# SCH.net
KiCad netlist of a schematic drawn in EasyEDA
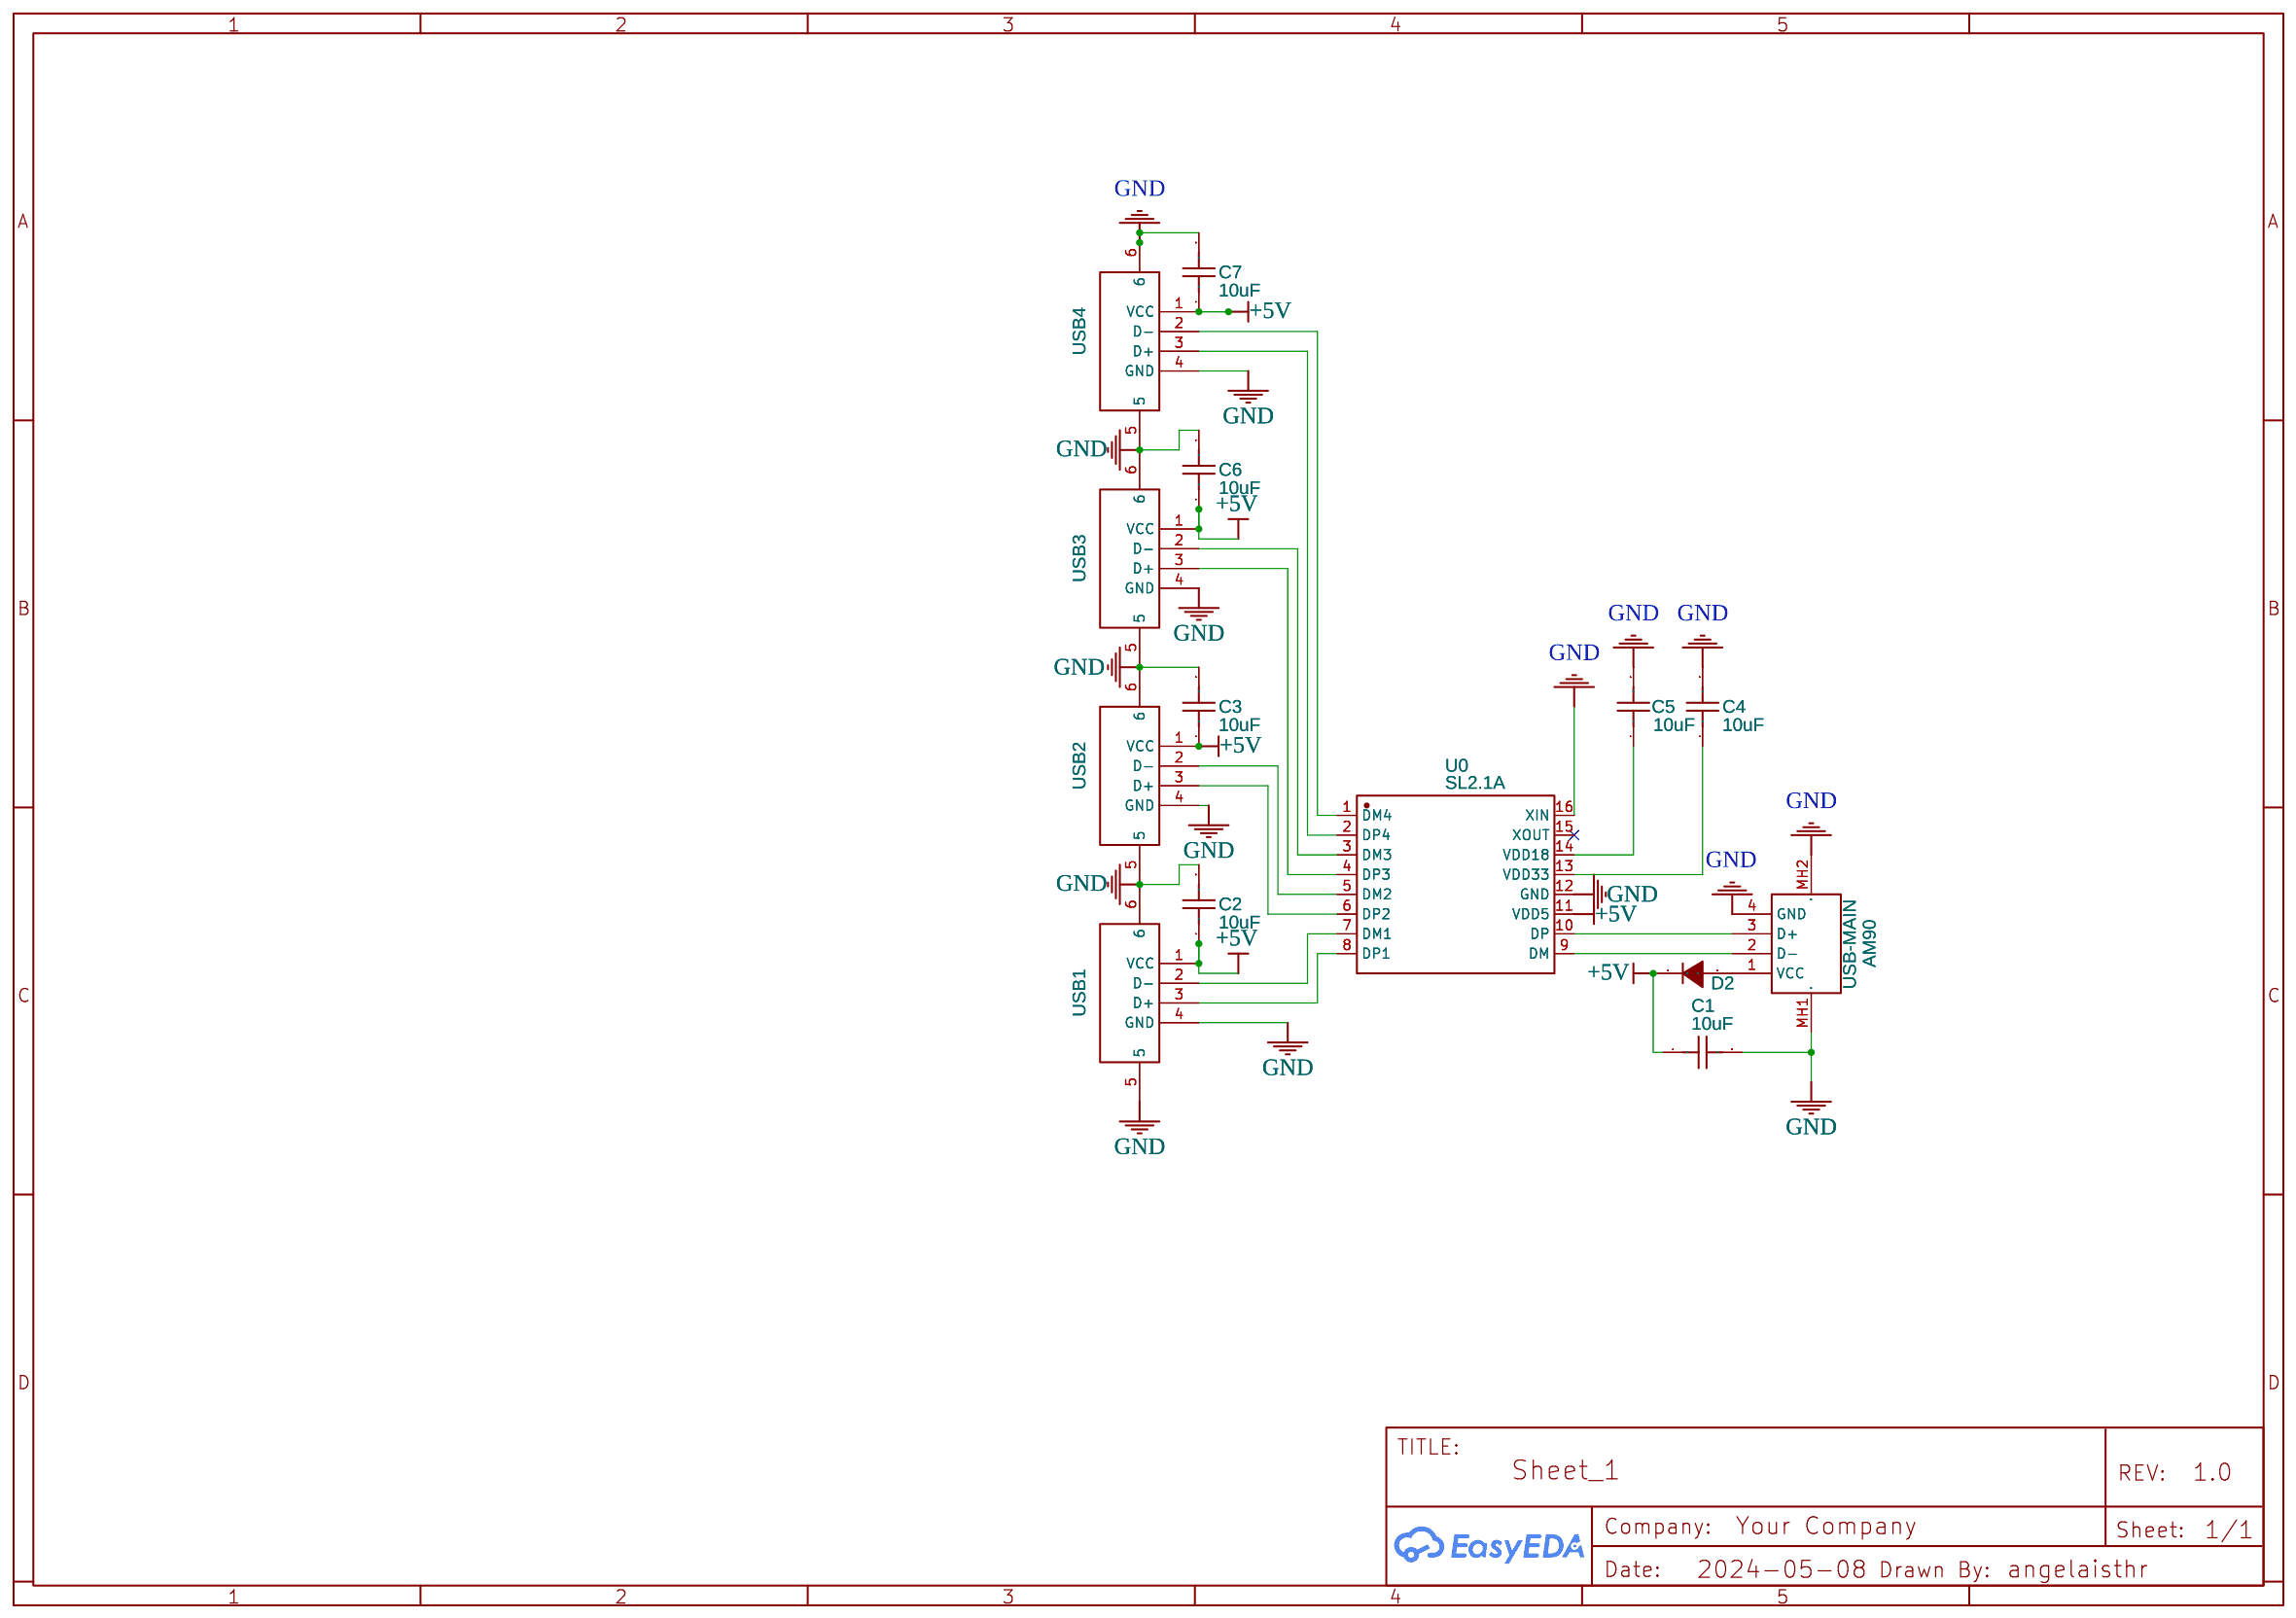
[diagram p0: schematic sheet]

(export (version "E")
  (design (tool "Eeschema 10.0.6"))
  (components
    (comp (ref "C1")
      (value "10uF")
      (fields
        (field (name "Manufacturer Part") "CL10A106KP8NNNC")
        (field (name "Manufacturer") "SAMSUNG(三星)")
      )
      (libsource (lib "") (part "CL10A106KP8NNNC"))
    )
    (comp (ref "C2")
      (value "10uF")
      (fields
        (field (name "Manufacturer Part") "CL10A106KP8NNNC")
        (field (name "Manufacturer") "SAMSUNG(三星)")
      )
      (libsource (lib "") (part "CL10A106KP8NNNC_1"))
    )
    (comp (ref "C3")
      (value "10uF")
      (fields
        (field (name "Manufacturer Part") "CL10A106KP8NNNC")
        (field (name "Manufacturer") "SAMSUNG(三星)")
      )
      (libsource (lib "") (part "CL10A106KP8NNNC_1"))
    )
    (comp (ref "C4")
      (value "10uF")
      (fields
        (field (name "Manufacturer Part") "CL10A106KP8NNNC")
        (field (name "Manufacturer") "SAMSUNG(三星)")
      )
      (libsource (lib "") (part "CL10A106KP8NNNC_1"))
    )
    (comp (ref "C5")
      (value "10uF")
      (fields
        (field (name "Manufacturer Part") "CL10A106KP8NNNC")
        (field (name "Manufacturer") "SAMSUNG(三星)")
      )
      (libsource (lib "") (part "CL10A106KP8NNNC_1"))
    )
    (comp (ref "C6")
      (value "10uF")
      (fields
        (field (name "Manufacturer Part") "CL10A106KP8NNNC")
        (field (name "Manufacturer") "SAMSUNG(三星)")
      )
      (libsource (lib "") (part "CL10A106KP8NNNC_1"))
    )
    (comp (ref "C7")
      (value "10uF")
      (fields
        (field (name "Manufacturer Part") "CL10A106KP8NNNC")
        (field (name "Manufacturer") "SAMSUNG(三星)")
      )
      (libsource (lib "") (part "CL10A106KP8NNNC_1"))
    )
    (comp (ref "D2")
      (value "NSR0320MW2T1G")
      (fields (field (name "Manufacturer") "onsemi(安森美)"))
      (libsource (lib "") (part "NSR0320MW2T1G"))
    )
    (comp (ref "U0")
      (value "SL2.1A")
      (fields (field (name "Manufacturer") "CoreChips(和芯润德)"))
      (libsource (lib "") (part "SL2.1A"))
    )
    (comp (ref "USB-MAIN")
      (value "AM90")
      (fields (field (name "Manufacturer") "SHOU HAN(首韩)"))
      (libsource (lib "") (part "AM90"))
    )
    (comp (ref "USB1")
      (value "USB-AF-90-14.4X13.6-H7.0-DIP")
      (fields (field (name "Manufacturer Part") "903-131A1011D10100") (field (name "Manufacturer") "精拓金"))
      (libsource (lib "") (part "USB-AF-90-14.4X13.6-H7.0-DIP"))
    )
    (comp (ref "USB2")
      (value "USB-AF-90-14.4X13.6-H7.0-DIP")
      (fields (field (name "Manufacturer Part") "903-131A1011D10100") (field (name "Manufacturer") "精拓金"))
      (libsource (lib "") (part "USB-AF-90-14.4X13.6-H7.0-DIP"))
    )
    (comp (ref "USB3")
      (value "USB-AF-90-14.4X13.6-H7.0-DIP")
      (fields (field (name "Manufacturer Part") "903-131A1011D10100") (field (name "Manufacturer") "精拓金"))
      (libsource (lib "") (part "USB-AF-90-14.4X13.6-H7.0-DIP"))
    )
    (comp (ref "USB4")
      (value "USB-AF-90-14.4X13.6-H7.0-DIP")
      (fields (field (name "Manufacturer Part") "903-131A1011D10100") (field (name "Manufacturer") "精拓金"))
      (libsource (lib "") (part "USB-AF-90-14.4X13.6-H7.0-DIP"))
    )
  )
  (nets
    (net (code "1") (name "+5V") (class "Default")
      (node (ref "C1") (pin "1") (pinfunction "1_1") (pintype "unspecified"))
      (node (ref "C2") (pin "1") (pinfunction "1_1") (pintype "unspecified"))
      (node (ref "C3") (pin "1") (pinfunction "1_1") (pintype "unspecified"))
      (node (ref "C6") (pin "1") (pinfunction "1_1") (pintype "unspecified"))
      (node (ref "C7") (pin "1") (pinfunction "1_1") (pintype "unspecified"))
      (node (ref "D2") (pin "1") (pinfunction "C_1") (pintype "unspecified"))
      (node (ref "U0") (pin "11") (pinfunction "VDD5_11") (pintype "unspecified"))
      (node (ref "USB1") (pin "1") (pinfunction "VCC_1") (pintype "unspecified"))
      (node (ref "USB2") (pin "1") (pinfunction "VCC_1") (pintype "unspecified"))
      (node (ref "USB3") (pin "1") (pinfunction "VCC_1") (pintype "unspecified"))
      (node (ref "USB4") (pin "1") (pinfunction "VCC_1") (pintype "unspecified"))
    )
    (net (code "2") (name "GND") (class "Default")
      (node (ref "C1") (pin "2") (pinfunction "2_2") (pintype "unspecified"))
      (node (ref "C2") (pin "2") (pinfunction "2_2") (pintype "unspecified"))
      (node (ref "C3") (pin "2") (pinfunction "2_2") (pintype "unspecified"))
      (node (ref "C4") (pin "2") (pinfunction "2_2") (pintype "unspecified"))
      (node (ref "C5") (pin "2") (pinfunction "2_2") (pintype "unspecified"))
      (node (ref "C6") (pin "2") (pinfunction "2_2") (pintype "unspecified"))
      (node (ref "C7") (pin "2") (pinfunction "2_2") (pintype "unspecified"))
      (node (ref "U0") (pin "12") (pinfunction "GND_12") (pintype "unspecified"))
      (node (ref "U0") (pin "16") (pinfunction "XIN_16") (pintype "unspecified"))
      (node (ref "USB-MAIN") (pin "4") (pinfunction "GND_4") (pintype "input"))
      (node (ref "USB-MAIN") (pin "MH1") (pinfunction "MH1_MH1") (pintype "unspecified"))
      (node (ref "USB-MAIN") (pin "MH2") (pinfunction "MH2_MH2") (pintype "unspecified"))
      (node (ref "USB1") (pin "4") (pinfunction "GND_4") (pintype "unspecified"))
      (node (ref "USB1") (pin "5") (pinfunction "5_5") (pintype "unspecified"))
      (node (ref "USB1") (pin "6") (pinfunction "6_6") (pintype "unspecified"))
      (node (ref "USB2") (pin "4") (pinfunction "GND_4") (pintype "unspecified"))
      (node (ref "USB2") (pin "5") (pinfunction "5_5") (pintype "unspecified"))
      (node (ref "USB2") (pin "6") (pinfunction "6_6") (pintype "unspecified"))
      (node (ref "USB3") (pin "4") (pinfunction "GND_4") (pintype "unspecified"))
      (node (ref "USB3") (pin "5") (pinfunction "5_5") (pintype "unspecified"))
      (node (ref "USB3") (pin "6") (pinfunction "6_6") (pintype "unspecified"))
      (node (ref "USB4") (pin "4") (pinfunction "GND_4") (pintype "unspecified"))
      (node (ref "USB4") (pin "5") (pinfunction "5_5") (pintype "unspecified"))
      (node (ref "USB4") (pin "6") (pinfunction "6_6") (pintype "unspecified"))
    )
    (net (code "3") (name "Net-(D2-A)") (class "Default")
      (node (ref "D2") (pin "2") (pinfunction "A_2") (pintype "unspecified"))
      (node (ref "USB-MAIN") (pin "1") (pinfunction "VCC_1") (pintype "input"))
    )
    (net (code "4") (name "Net-(U0-DM)") (class "Default")
      (node (ref "U0") (pin "9") (pinfunction "DM_9") (pintype "unspecified"))
      (node (ref "USB-MAIN") (pin "2") (pinfunction "D-_2") (pintype "input"))
    )
    (net (code "5") (name "Net-(U0-DM1)") (class "Default")
      (node (ref "U0") (pin "7") (pinfunction "DM1_7") (pintype "unspecified"))
      (node (ref "USB1") (pin "2") (pinfunction "D-_2") (pintype "unspecified"))
    )
    (net (code "6") (name "Net-(U0-DM2)") (class "Default")
      (node (ref "U0") (pin "5") (pinfunction "DM2_5") (pintype "unspecified"))
      (node (ref "USB2") (pin "2") (pinfunction "D-_2") (pintype "unspecified"))
    )
    (net (code "7") (name "Net-(U0-DM3)") (class "Default")
      (node (ref "U0") (pin "3") (pinfunction "DM3_3") (pintype "unspecified"))
      (node (ref "USB3") (pin "2") (pinfunction "D-_2") (pintype "unspecified"))
    )
    (net (code "8") (name "Net-(U0-DM4)") (class "Default")
      (node (ref "U0") (pin "1") (pinfunction "DM4_1") (pintype "unspecified"))
      (node (ref "USB4") (pin "2") (pinfunction "D-_2") (pintype "unspecified"))
    )
    (net (code "9") (name "Net-(U0-DP)") (class "Default")
      (node (ref "U0") (pin "10") (pinfunction "DP_10") (pintype "unspecified"))
      (node (ref "USB-MAIN") (pin "3") (pinfunction "D+_3") (pintype "input"))
    )
    (net (code "10") (name "Net-(U0-DP1)") (class "Default")
      (node (ref "U0") (pin "8") (pinfunction "DP1_8") (pintype "unspecified"))
      (node (ref "USB1") (pin "3") (pinfunction "D+_3") (pintype "unspecified"))
    )
    (net (code "11") (name "Net-(U0-DP2)") (class "Default")
      (node (ref "U0") (pin "6") (pinfunction "DP2_6") (pintype "unspecified"))
      (node (ref "USB2") (pin "3") (pinfunction "D+_3") (pintype "unspecified"))
    )
    (net (code "12") (name "Net-(U0-DP3)") (class "Default")
      (node (ref "U0") (pin "4") (pinfunction "DP3_4") (pintype "unspecified"))
      (node (ref "USB3") (pin "3") (pinfunction "D+_3") (pintype "unspecified"))
    )
    (net (code "13") (name "Net-(U0-DP4)") (class "Default")
      (node (ref "U0") (pin "2") (pinfunction "DP4_2") (pintype "unspecified"))
      (node (ref "USB4") (pin "3") (pinfunction "D+_3") (pintype "unspecified"))
    )
    (net (code "14") (name "Net-(U0-VDD18)") (class "Default")
      (node (ref "C5") (pin "1") (pinfunction "1_1") (pintype "unspecified"))
      (node (ref "U0") (pin "14") (pinfunction "VDD18_14") (pintype "unspecified"))
    )
    (net (code "15") (name "Net-(U0-VDD33)") (class "Default")
      (node (ref "C4") (pin "1") (pinfunction "1_1") (pintype "unspecified"))
      (node (ref "U0") (pin "13") (pinfunction "VDD33_13") (pintype "unspecified"))
    )
    (net (code "16") (name "unconnected-(U0-XOUT-Pad15)") (class "Default")
      (node (ref "U0") (pin "15") (pinfunction "XOUT_15") (pintype "unspecified+no_connect"))
    )
  )
)
